# INT_REVA.net
KiCad netlist of a schematic drawn in Altium Designer
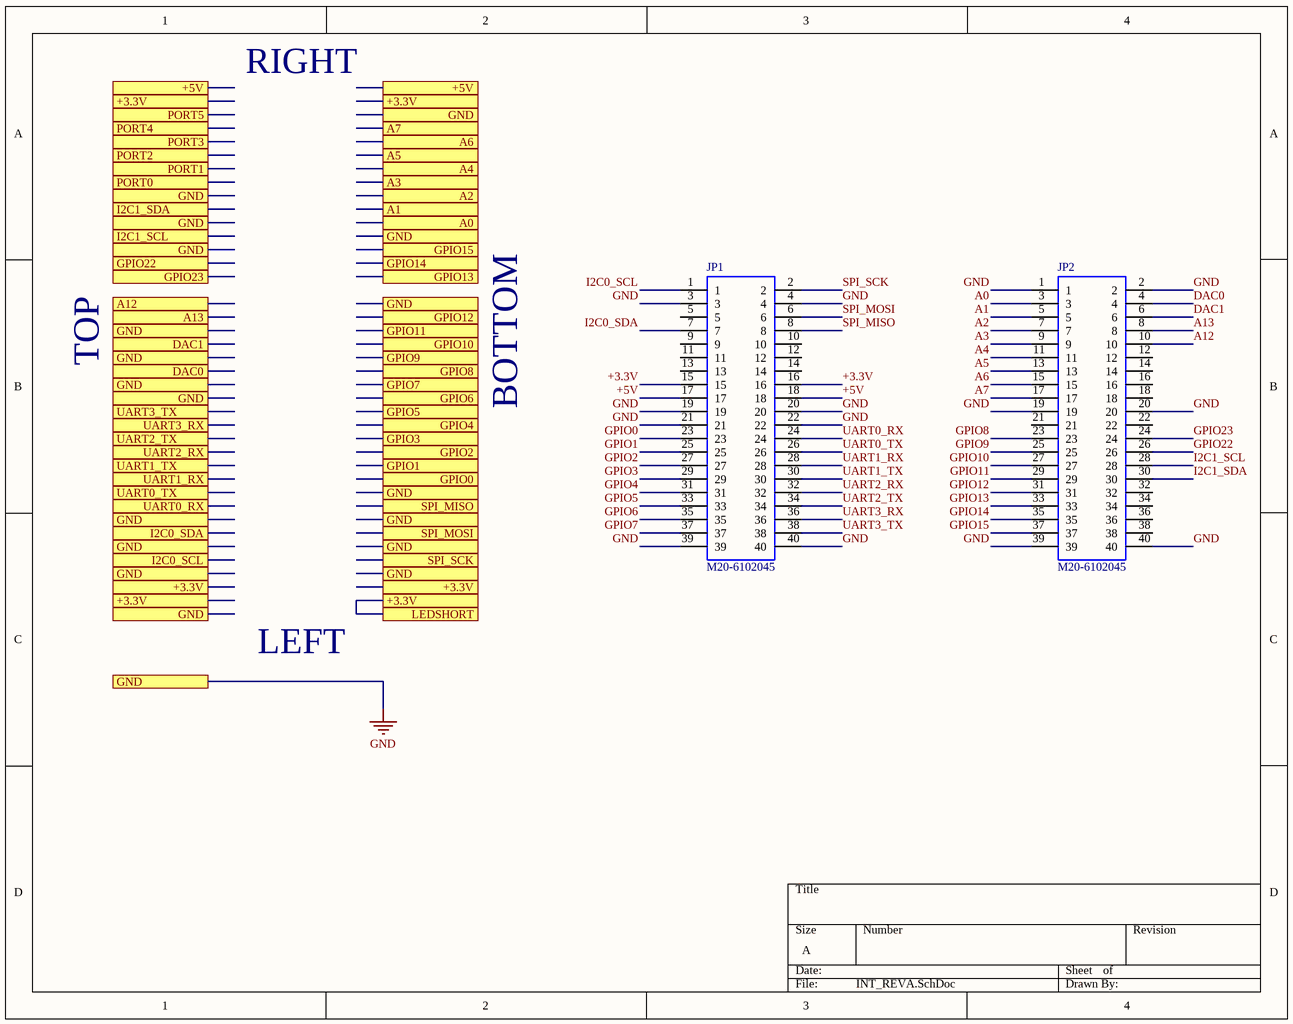
[diagram p0: INT_REVA.SchDoc]

(export (version "E")
  (design (tool "Eeschema 10.0.6"))
  (components
    (comp (ref "JP1")
      (value "M20-6102045")
      (footprint "RHDR40W66P254_2X20_5146X500X1105P:RHDR40W66P254_2X20_5146X500X1105P")
      (description "PC / 104 Connectors PC104 STACK CONNECT 20+20 HI TEMP AU")
      (fields (field (name "MOUSER PART NUMBER") "855-M20-6102045"))
      (libsource (lib "INT_REVA") (part "M20-6102045"))
    )
    (comp (ref "JP2")
      (value "M20-6102045")
      (footprint "RHDR40W66P254_2X20_5146X500X1105P:RHDR40W66P254_2X20_5146X500X1105P")
      (description "PC / 104 Connectors PC104 STACK CONNECT 20+20 HI TEMP AU")
      (fields (field (name "MOUSER PART NUMBER") "855-M20-6102045"))
      (libsource (lib "INT_REVA") (part "M20-6102045"))
    )
  )
  (nets
    (net (code "1") (name "/+3.3V") (class "Default")
      (node (ref "JP1") (pin "15") (pinfunction "15_15") (pintype "passive"))
      (node (ref "JP1") (pin "16") (pinfunction "16_16") (pintype "passive"))
    )
    (net (code "2") (name "/+5V") (class "Default")
      (node (ref "JP1") (pin "17") (pinfunction "17_17") (pintype "passive"))
      (node (ref "JP1") (pin "18") (pinfunction "18_18") (pintype "passive"))
    )
    (net (code "3") (name "/A0") (class "Default")
      (node (ref "JP2") (pin "3") (pinfunction "3_3") (pintype "passive"))
    )
    (net (code "4") (name "/A1") (class "Default")
      (node (ref "JP2") (pin "5") (pinfunction "5_5") (pintype "passive"))
    )
    (net (code "5") (name "/A2") (class "Default")
      (node (ref "JP2") (pin "7") (pinfunction "7_7") (pintype "passive"))
    )
    (net (code "6") (name "/A3") (class "Default")
      (node (ref "JP2") (pin "9") (pinfunction "9_9") (pintype "passive"))
    )
    (net (code "7") (name "/A4") (class "Default")
      (node (ref "JP2") (pin "11") (pinfunction "11_11") (pintype "passive"))
    )
    (net (code "8") (name "/A5") (class "Default")
      (node (ref "JP2") (pin "13") (pinfunction "13_13") (pintype "passive"))
    )
    (net (code "9") (name "/A6") (class "Default")
      (node (ref "JP2") (pin "15") (pinfunction "15_15") (pintype "passive"))
    )
    (net (code "10") (name "/A7") (class "Default")
      (node (ref "JP2") (pin "17") (pinfunction "17_17") (pintype "passive"))
    )
    (net (code "11") (name "/A12") (class "Default")
      (node (ref "JP2") (pin "10") (pinfunction "10_10") (pintype "passive"))
    )
    (net (code "12") (name "/A13") (class "Default")
      (node (ref "JP2") (pin "8") (pinfunction "8_8") (pintype "passive"))
    )
    (net (code "13") (name "/DAC0") (class "Default")
      (node (ref "JP2") (pin "4") (pinfunction "4_4") (pintype "passive"))
    )
    (net (code "14") (name "/DAC1") (class "Default")
      (node (ref "JP2") (pin "6") (pinfunction "6_6") (pintype "passive"))
    )
    (net (code "15") (name "/GPIO0") (class "Default")
      (node (ref "JP1") (pin "23") (pinfunction "23_23") (pintype "passive"))
    )
    (net (code "16") (name "/GPIO1") (class "Default")
      (node (ref "JP1") (pin "25") (pinfunction "25_25") (pintype "passive"))
    )
    (net (code "17") (name "/GPIO2") (class "Default")
      (node (ref "JP1") (pin "27") (pinfunction "27_27") (pintype "passive"))
    )
    (net (code "18") (name "/GPIO3") (class "Default")
      (node (ref "JP1") (pin "29") (pinfunction "29_29") (pintype "passive"))
    )
    (net (code "19") (name "/GPIO4") (class "Default")
      (node (ref "JP1") (pin "31") (pinfunction "31_31") (pintype "passive"))
    )
    (net (code "20") (name "/GPIO5") (class "Default")
      (node (ref "JP1") (pin "33") (pinfunction "33_33") (pintype "passive"))
    )
    (net (code "21") (name "/GPIO6") (class "Default")
      (node (ref "JP1") (pin "35") (pinfunction "35_35") (pintype "passive"))
    )
    (net (code "22") (name "/GPIO7") (class "Default")
      (node (ref "JP1") (pin "37") (pinfunction "37_37") (pintype "passive"))
    )
    (net (code "23") (name "/GPIO8") (class "Default")
      (node (ref "JP2") (pin "23") (pinfunction "23_23") (pintype "passive"))
    )
    (net (code "24") (name "/GPIO9") (class "Default")
      (node (ref "JP2") (pin "25") (pinfunction "25_25") (pintype "passive"))
    )
    (net (code "25") (name "/GPIO10") (class "Default")
      (node (ref "JP2") (pin "27") (pinfunction "27_27") (pintype "passive"))
    )
    (net (code "26") (name "/GPIO11") (class "Default")
      (node (ref "JP2") (pin "29") (pinfunction "29_29") (pintype "passive"))
    )
    (net (code "27") (name "/GPIO12") (class "Default")
      (node (ref "JP2") (pin "31") (pinfunction "31_31") (pintype "passive"))
    )
    (net (code "28") (name "/GPIO13") (class "Default")
      (node (ref "JP2") (pin "33") (pinfunction "33_33") (pintype "passive"))
    )
    (net (code "29") (name "/GPIO14") (class "Default")
      (node (ref "JP2") (pin "35") (pinfunction "35_35") (pintype "passive"))
    )
    (net (code "30") (name "/GPIO15") (class "Default")
      (node (ref "JP2") (pin "37") (pinfunction "37_37") (pintype "passive"))
    )
    (net (code "31") (name "/GPIO22") (class "Default")
      (node (ref "JP2") (pin "26") (pinfunction "26_26") (pintype "passive"))
    )
    (net (code "32") (name "/GPIO23") (class "Default")
      (node (ref "JP2") (pin "24") (pinfunction "24_24") (pintype "passive"))
    )
    (net (code "33") (name "/I2C0_SCL") (class "Default")
      (node (ref "JP1") (pin "1") (pinfunction "1_1") (pintype "passive"))
    )
    (net (code "34") (name "/I2C0_SDA") (class "Default")
      (node (ref "JP1") (pin "7") (pinfunction "7_7") (pintype "passive"))
    )
    (net (code "35") (name "/I2C1_SCL") (class "Default")
      (node (ref "JP2") (pin "28") (pinfunction "28_28") (pintype "passive"))
    )
    (net (code "36") (name "/I2C1_SDA") (class "Default")
      (node (ref "JP2") (pin "30") (pinfunction "30_30") (pintype "passive"))
    )
    (net (code "43") (name "/SPI_MISO") (class "Default")
      (node (ref "JP1") (pin "8") (pinfunction "8_8") (pintype "passive"))
    )
    (net (code "44") (name "/SPI_MOSI") (class "Default")
      (node (ref "JP1") (pin "6") (pinfunction "6_6") (pintype "passive"))
    )
    (net (code "45") (name "/SPI_SCK") (class "Default")
      (node (ref "JP1") (pin "2") (pinfunction "2_2") (pintype "passive"))
    )
    (net (code "46") (name "/UART0_RX") (class "Default")
      (node (ref "JP1") (pin "24") (pinfunction "24_24") (pintype "passive"))
    )
    (net (code "47") (name "/UART0_TX") (class "Default")
      (node (ref "JP1") (pin "26") (pinfunction "26_26") (pintype "passive"))
    )
    (net (code "48") (name "/UART1_RX") (class "Default")
      (node (ref "JP1") (pin "28") (pinfunction "28_28") (pintype "passive"))
    )
    (net (code "49") (name "/UART1_TX") (class "Default")
      (node (ref "JP1") (pin "30") (pinfunction "30_30") (pintype "passive"))
    )
    (net (code "50") (name "/UART2_RX") (class "Default")
      (node (ref "JP1") (pin "32") (pinfunction "32_32") (pintype "passive"))
    )
    (net (code "51") (name "/UART2_TX") (class "Default")
      (node (ref "JP1") (pin "34") (pinfunction "34_34") (pintype "passive"))
    )
    (net (code "52") (name "/UART3_RX") (class "Default")
      (node (ref "JP1") (pin "36") (pinfunction "36_36") (pintype "passive"))
    )
    (net (code "53") (name "/UART3_TX") (class "Default")
      (node (ref "JP1") (pin "38") (pinfunction "38_38") (pintype "passive"))
    )
    (net (code "54") (name "GND") (class "Default")
      (node (ref "JP1") (pin "19") (pinfunction "19_19") (pintype "passive"))
      (node (ref "JP1") (pin "20") (pinfunction "20_20") (pintype "passive"))
      (node (ref "JP1") (pin "21") (pinfunction "21_21") (pintype "passive"))
      (node (ref "JP1") (pin "22") (pinfunction "22_22") (pintype "passive"))
      (node (ref "JP1") (pin "3") (pinfunction "3_3") (pintype "passive"))
      (node (ref "JP1") (pin "39") (pinfunction "39_39") (pintype "passive"))
      (node (ref "JP1") (pin "4") (pinfunction "4_4") (pintype "passive"))
      (node (ref "JP1") (pin "40") (pinfunction "40_40") (pintype "passive"))
      (node (ref "JP2") (pin "1") (pinfunction "1_1") (pintype "passive"))
      (node (ref "JP2") (pin "19") (pinfunction "19_19") (pintype "passive"))
      (node (ref "JP2") (pin "2") (pinfunction "2_2") (pintype "passive"))
      (node (ref "JP2") (pin "20") (pinfunction "20_20") (pintype "passive"))
      (node (ref "JP2") (pin "39") (pinfunction "39_39") (pintype "passive"))
      (node (ref "JP2") (pin "40") (pinfunction "40_40") (pintype "passive"))
    )
    (net (code "55") (name "unconnected-(JP1-Pad5)") (class "Default")
      (node (ref "JP1") (pin "5") (pinfunction "5_5") (pintype "passive"))
    )
    (net (code "56") (name "unconnected-(JP1-Pad9)") (class "Default")
      (node (ref "JP1") (pin "9") (pinfunction "9_9") (pintype "passive"))
    )
    (net (code "57") (name "unconnected-(JP1-Pad10)") (class "Default")
      (node (ref "JP1") (pin "10") (pinfunction "10_10") (pintype "passive"))
    )
    (net (code "58") (name "unconnected-(JP1-Pad11)") (class "Default")
      (node (ref "JP1") (pin "11") (pinfunction "11_11") (pintype "passive"))
    )
    (net (code "59") (name "unconnected-(JP1-Pad12)") (class "Default")
      (node (ref "JP1") (pin "12") (pinfunction "12_12") (pintype "passive"))
    )
    (net (code "60") (name "unconnected-(JP1-Pad13)") (class "Default")
      (node (ref "JP1") (pin "13") (pinfunction "13_13") (pintype "passive"))
    )
    (net (code "61") (name "unconnected-(JP1-Pad14)") (class "Default")
      (node (ref "JP1") (pin "14") (pinfunction "14_14") (pintype "passive"))
    )
    (net (code "62") (name "unconnected-(JP2-Pad12)") (class "Default")
      (node (ref "JP2") (pin "12") (pinfunction "12_12") (pintype "passive"))
    )
    (net (code "63") (name "unconnected-(JP2-Pad14)") (class "Default")
      (node (ref "JP2") (pin "14") (pinfunction "14_14") (pintype "passive"))
    )
    (net (code "64") (name "unconnected-(JP2-Pad16)") (class "Default")
      (node (ref "JP2") (pin "16") (pinfunction "16_16") (pintype "passive"))
    )
    (net (code "65") (name "unconnected-(JP2-Pad18)") (class "Default")
      (node (ref "JP2") (pin "18") (pinfunction "18_18") (pintype "passive"))
    )
    (net (code "66") (name "unconnected-(JP2-Pad21)") (class "Default")
      (node (ref "JP2") (pin "21") (pinfunction "21_21") (pintype "passive"))
    )
    (net (code "67") (name "unconnected-(JP2-Pad22)") (class "Default")
      (node (ref "JP2") (pin "22") (pinfunction "22_22") (pintype "passive"))
    )
    (net (code "68") (name "unconnected-(JP2-Pad32)") (class "Default")
      (node (ref "JP2") (pin "32") (pinfunction "32_32") (pintype "passive"))
    )
    (net (code "69") (name "unconnected-(JP2-Pad34)") (class "Default")
      (node (ref "JP2") (pin "34") (pinfunction "34_34") (pintype "passive"))
    )
    (net (code "70") (name "unconnected-(JP2-Pad36)") (class "Default")
      (node (ref "JP2") (pin "36") (pinfunction "36_36") (pintype "passive"))
    )
    (net (code "71") (name "unconnected-(JP2-Pad38)") (class "Default")
      (node (ref "JP2") (pin "38") (pinfunction "38_38") (pintype "passive"))
    )
  )
)
